# Powerswitch_dengan_fitur_reset.net
KiCad netlist of a schematic drawn in EAGLE
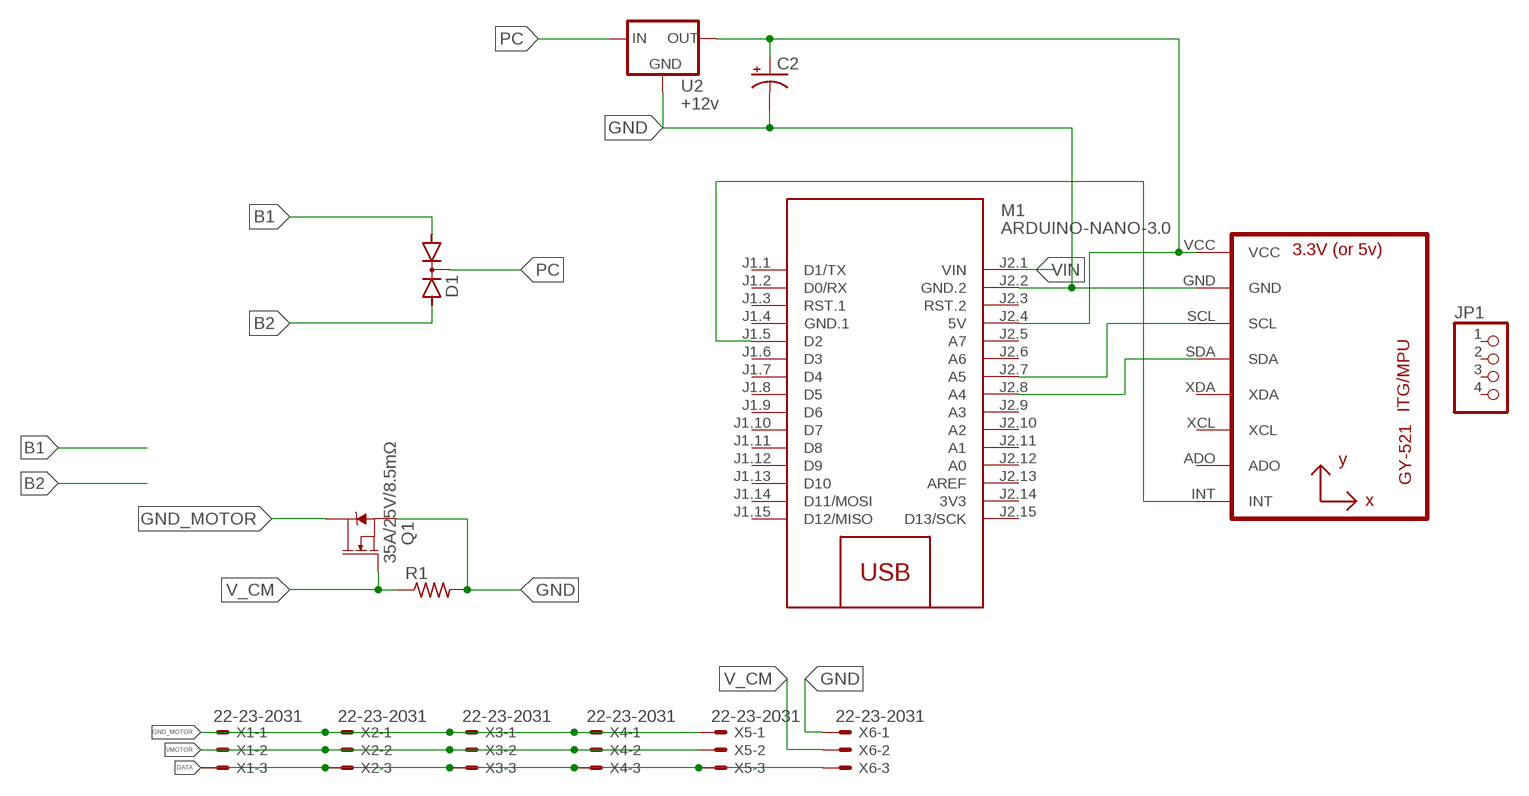
[diagram p0: schematic, sheet 1]

(export (version "E")
  (design (tool "Eeschema 10.0.6"))
  (components
    (comp (ref "C2")
      (value "CPOL-USE2-5")
      (footprint "eagle-import:E2-5")
      (libsource (lib "eagle-import") (part "CPOL-USE2-5"))
    )
    (comp (ref "D1")
      (value "DIODE-2AC|CATO220H")
      (footprint "eagle-import:TO220AB")
      (libsource (lib "eagle-import") (part "DIODE-2AC|CATO220H"))
    )
    (comp (ref "JP1")
      (value "PINHD-1X4")
      (footprint "eagle-import:1X04")
      (libsource (lib "eagle-import") (part "PINHD-1X4"))
    )
    (comp (ref "M1")
      (value "ARDUINO-NANO-3.0")
      (footprint "eagle-import:ARDUINO-NANO-3.0")
      (libsource (lib "eagle-import") (part "ARDUINO-NANO-3.0"))
    )
    (comp (ref "Q1")
      (value "35A/25V/8.5mΩ")
      (footprint "eagle-import:DPAK")
      (libsource (lib "eagle-import") (part "MOSFET-NCH-FDD8780"))
    )
    (comp (ref "R1")
      (value "R-US_0207/10")
      (footprint "eagle-import:0207_10")
      (libsource (lib "eagle-import") (part "R-US_0207/10"))
    )
    (comp (ref "U1")
      (value "GY-521MPU6050")
      (footprint "eagle-import:GY-521")
      (libsource (lib "eagle-import") (part "GY-521MPU6050"))
    )
    (comp (ref "U2")
      (value "+12v")
      (footprint "eagle-import:TO-252")
      (libsource (lib "eagle-import") (part "V_REG_78XX7812"))
    )
    (comp (ref "X1")
      (value "22-23-2031")
      (footprint "eagle-import:22-23-2031")
      (fields (field (name "MF") "MOLEX"))
      (libsource (lib "eagle-import") (part "22-23-2031"))
    )
    (comp (ref "X2")
      (value "22-23-2031")
      (footprint "eagle-import:22-23-2031")
      (fields (field (name "MF") "MOLEX"))
      (libsource (lib "eagle-import") (part "22-23-2031"))
    )
    (comp (ref "X3")
      (value "22-23-2031")
      (footprint "eagle-import:22-23-2031")
      (fields (field (name "MF") "MOLEX"))
      (libsource (lib "eagle-import") (part "22-23-2031"))
    )
    (comp (ref "X4")
      (value "22-23-2031")
      (footprint "eagle-import:22-23-2031")
      (fields (field (name "MF") "MOLEX"))
      (libsource (lib "eagle-import") (part "22-23-2031"))
    )
    (comp (ref "X5")
      (value "22-23-2031")
      (footprint "eagle-import:22-23-2031")
      (fields (field (name "MF") "MOLEX"))
      (libsource (lib "eagle-import") (part "22-23-2031"))
    )
    (comp (ref "X6")
      (value "22-23-2031")
      (footprint "eagle-import:22-23-2031")
      (fields (field (name "MF") "MOLEX"))
      (libsource (lib "eagle-import") (part "22-23-2031"))
    )
  )
  (nets
    (net (code "1") (name "/3V3") (class "Default")
      (node (ref "M1") (pin "J2.14") (pinfunction "3V3_J2.14") (pintype "power_in"))
    )
    (net (code "2") (name "/GND.1") (class "Default")
      (node (ref "M1") (pin "J1.4") (pinfunction "GND.1_J1.4") (pintype "power_in"))
    )
    (net (code "3") (name "B1") (class "Default")
      (node (ref "D1") (pin "A1") (pinfunction "A1_A1") (pintype "passive"))
    )
    (net (code "4") (name "B2") (class "Default")
      (node (ref "D1") (pin "A2") (pinfunction "A2_A2") (pintype "passive"))
    )
    (net (code "5") (name "DATA") (class "Default")
      (node (ref "X1") (pin "3") (pinfunction "S_3") (pintype "passive"))
      (node (ref "X2") (pin "3") (pinfunction "S_3") (pintype "passive"))
      (node (ref "X3") (pin "3") (pinfunction "S_3") (pintype "passive"))
      (node (ref "X4") (pin "3") (pinfunction "S_3") (pintype "passive"))
      (node (ref "X5") (pin "3") (pinfunction "S_3") (pintype "passive"))
      (node (ref "X6") (pin "3") (pinfunction "S_3") (pintype "passive"))
    )
    (net (code "6") (name "GND") (class "Default")
      (node (ref "C2") (pin "-") (pinfunction "-_-") (pintype "passive"))
      (node (ref "M1") (pin "J2.2") (pinfunction "GND.2_J2.2") (pintype "power_in"))
      (node (ref "Q1") (pin "3") (pinfunction "S_3") (pintype "bidirectional"))
      (node (ref "R1") (pin "2") (pinfunction "2_2") (pintype "passive"))
      (node (ref "U1") (pin "GND") (pinfunction "GND_GND") (pintype "bidirectional"))
      (node (ref "U2") (pin "3") (pinfunction "GND_3") (pintype "input"))
      (node (ref "X6") (pin "1") (pinfunction "S_1") (pintype "passive"))
    )
    (net (code "7") (name "GND_MOTOR") (class "Default")
      (node (ref "Q1") (pin "4") (pinfunction "D_4") (pintype "bidirectional"))
      (node (ref "X1") (pin "1") (pinfunction "S_1") (pintype "passive"))
      (node (ref "X2") (pin "1") (pinfunction "S_1") (pintype "passive"))
      (node (ref "X3") (pin "1") (pinfunction "S_1") (pintype "passive"))
      (node (ref "X4") (pin "1") (pinfunction "S_1") (pintype "passive"))
      (node (ref "X5") (pin "1") (pinfunction "S_1") (pintype "passive"))
    )
    (net (code "8") (name "Net-(M1-5V)") (class "Default")
      (node (ref "C2") (pin "+") (pinfunction "+_+") (pintype "passive"))
      (node (ref "M1") (pin "J2.4") (pinfunction "5V_J2.4") (pintype "power_in"))
      (node (ref "U1") (pin "VCC") (pinfunction "VCC_VCC") (pintype "bidirectional"))
      (node (ref "U2") (pin "2") (pinfunction "OUT_2") (pintype "passive"))
    )
    (net (code "9") (name "Net-(M1-A4)") (class "Default")
      (node (ref "M1") (pin "J2.8") (pinfunction "A4_J2.8") (pintype "bidirectional"))
      (node (ref "U1") (pin "SDA") (pinfunction "SDA_SDA") (pintype "bidirectional"))
    )
    (net (code "10") (name "Net-(M1-A5)") (class "Default")
      (node (ref "M1") (pin "J2.7") (pinfunction "A5_J2.7") (pintype "bidirectional"))
      (node (ref "U1") (pin "SCL") (pinfunction "SCL_SCL") (pintype "bidirectional"))
    )
    (net (code "11") (name "Net-(M1-D2)") (class "Default")
      (node (ref "M1") (pin "J1.5") (pinfunction "D2_J1.5") (pintype "bidirectional"))
      (node (ref "U1") (pin "INT") (pinfunction "INT_INT") (pintype "bidirectional"))
    )
    (net (code "12") (name "PC") (class "Default")
      (node (ref "D1") (pin "C") (pinfunction "C_C") (pintype "passive"))
      (node (ref "U2") (pin "1") (pinfunction "IN_1") (pintype "input"))
    )
    (net (code "13") (name "VIN") (class "Default")
      (node (ref "M1") (pin "J2.1") (pinfunction "VIN_J2.1") (pintype "power_in"))
    )
    (net (code "14") (name "VMOTOR") (class "Default")
      (node (ref "X1") (pin "2") (pinfunction "S_2") (pintype "passive"))
      (node (ref "X2") (pin "2") (pinfunction "S_2") (pintype "passive"))
      (node (ref "X3") (pin "2") (pinfunction "S_2") (pintype "passive"))
      (node (ref "X4") (pin "2") (pinfunction "S_2") (pintype "passive"))
      (node (ref "X5") (pin "2") (pinfunction "S_2") (pintype "passive"))
    )
    (net (code "15") (name "V_CM") (class "Default")
      (node (ref "Q1") (pin "1") (pinfunction "G_1") (pintype "bidirectional"))
      (node (ref "R1") (pin "1") (pinfunction "1_1") (pintype "passive"))
      (node (ref "X6") (pin "2") (pinfunction "S_2") (pintype "passive"))
    )
    (net (code "16") (name "unconnected-(JP1-Pad1)") (class "Default")
      (node (ref "JP1") (pin "1") (pinfunction "1_1") (pintype "passive"))
    )
    (net (code "17") (name "unconnected-(JP1-Pad2)") (class "Default")
      (node (ref "JP1") (pin "2") (pinfunction "2_2") (pintype "passive"))
    )
    (net (code "18") (name "unconnected-(JP1-Pad3)") (class "Default")
      (node (ref "JP1") (pin "3") (pinfunction "3_3") (pintype "passive"))
    )
    (net (code "19") (name "unconnected-(JP1-Pad4)") (class "Default")
      (node (ref "JP1") (pin "4") (pinfunction "4_4") (pintype "passive"))
    )
    (net (code "20") (name "unconnected-(M1-A0-PadJ2.12)") (class "Default")
      (node (ref "M1") (pin "J2.12") (pinfunction "A0_J2.12") (pintype "bidirectional"))
    )
    (net (code "21") (name "unconnected-(M1-A1-PadJ2.11)") (class "Default")
      (node (ref "M1") (pin "J2.11") (pinfunction "A1_J2.11") (pintype "bidirectional"))
    )
    (net (code "22") (name "unconnected-(M1-A2-PadJ2.10)") (class "Default")
      (node (ref "M1") (pin "J2.10") (pinfunction "A2_J2.10") (pintype "bidirectional"))
    )
    (net (code "23") (name "unconnected-(M1-A3-PadJ2.9)") (class "Default")
      (node (ref "M1") (pin "J2.9") (pinfunction "A3_J2.9") (pintype "bidirectional"))
    )
    (net (code "24") (name "unconnected-(M1-A6-PadJ2.6)") (class "Default")
      (node (ref "M1") (pin "J2.6") (pinfunction "A6_J2.6") (pintype "bidirectional"))
    )
    (net (code "25") (name "unconnected-(M1-A7-PadJ2.5)") (class "Default")
      (node (ref "M1") (pin "J2.5") (pinfunction "A7_J2.5") (pintype "bidirectional"))
    )
    (net (code "26") (name "unconnected-(M1-AREF-PadJ2.13)") (class "Default")
      (node (ref "M1") (pin "J2.13") (pinfunction "AREF_J2.13") (pintype "bidirectional"))
    )
    (net (code "27") (name "unconnected-(M1-D0{slash}RX-PadJ1.2)") (class "Default")
      (node (ref "M1") (pin "J1.2") (pinfunction "D0/RX_J1.2") (pintype "bidirectional"))
    )
    (net (code "28") (name "unconnected-(M1-D1{slash}TX-PadJ1.1)") (class "Default")
      (node (ref "M1") (pin "J1.1") (pinfunction "D1/TX_J1.1") (pintype "bidirectional"))
    )
    (net (code "29") (name "unconnected-(M1-D3-PadJ1.6)") (class "Default")
      (node (ref "M1") (pin "J1.6") (pinfunction "D3_J1.6") (pintype "bidirectional"))
    )
    (net (code "30") (name "unconnected-(M1-D4-PadJ1.7)") (class "Default")
      (node (ref "M1") (pin "J1.7") (pinfunction "D4_J1.7") (pintype "bidirectional"))
    )
    (net (code "31") (name "unconnected-(M1-D5-PadJ1.8)") (class "Default")
      (node (ref "M1") (pin "J1.8") (pinfunction "D5_J1.8") (pintype "bidirectional"))
    )
    (net (code "32") (name "unconnected-(M1-D6-PadJ1.9)") (class "Default")
      (node (ref "M1") (pin "J1.9") (pinfunction "D6_J1.9") (pintype "bidirectional"))
    )
    (net (code "33") (name "unconnected-(M1-D7-PadJ1.10)") (class "Default")
      (node (ref "M1") (pin "J1.10") (pinfunction "D7_J1.10") (pintype "bidirectional"))
    )
    (net (code "34") (name "unconnected-(M1-D8-PadJ1.11)") (class "Default")
      (node (ref "M1") (pin "J1.11") (pinfunction "D8_J1.11") (pintype "bidirectional"))
    )
    (net (code "35") (name "unconnected-(M1-D9-PadJ1.12)") (class "Default")
      (node (ref "M1") (pin "J1.12") (pinfunction "D9_J1.12") (pintype "bidirectional"))
    )
    (net (code "36") (name "unconnected-(M1-D10-PadJ1.13)") (class "Default")
      (node (ref "M1") (pin "J1.13") (pinfunction "D10_J1.13") (pintype "bidirectional"))
    )
    (net (code "37") (name "unconnected-(M1-D11{slash}MOSI-PadJ1.14)") (class "Default")
      (node (ref "M1") (pin "J1.14") (pinfunction "D11/MOSI_J1.14") (pintype "bidirectional"))
    )
    (net (code "38") (name "unconnected-(M1-D12{slash}MISO-PadJ1.15)") (class "Default")
      (node (ref "M1") (pin "J1.15") (pinfunction "D12/MISO_J1.15") (pintype "bidirectional"))
    )
    (net (code "39") (name "unconnected-(M1-D13{slash}SCK-PadJ2.15)") (class "Default")
      (node (ref "M1") (pin "J2.15") (pinfunction "D13/SCK_J2.15") (pintype "bidirectional"))
    )
    (net (code "40") (name "unconnected-(M1-RST.1-PadJ1.3)") (class "Default")
      (node (ref "M1") (pin "J1.3") (pinfunction "RST.1_J1.3") (pintype "bidirectional"))
    )
    (net (code "41") (name "unconnected-(M1-RST.2-PadJ2.3)") (class "Default")
      (node (ref "M1") (pin "J2.3") (pinfunction "RST.2_J2.3") (pintype "bidirectional"))
    )
    (net (code "42") (name "unconnected-(U1-PadADO)") (class "Default")
      (node (ref "U1") (pin "ADO") (pinfunction "ADO_ADO") (pintype "bidirectional"))
    )
    (net (code "43") (name "unconnected-(U1-PadXCL)") (class "Default")
      (node (ref "U1") (pin "XCL") (pinfunction "XCL_XCL") (pintype "bidirectional"))
    )
    (net (code "44") (name "unconnected-(U1-PadXDA)") (class "Default")
      (node (ref "U1") (pin "XDA") (pinfunction "XDA_XDA") (pintype "bidirectional"))
    )
  )
)
